# SSFocuser-C-TMC2208.net
KiCad netlist of a schematic drawn in Altium Designer
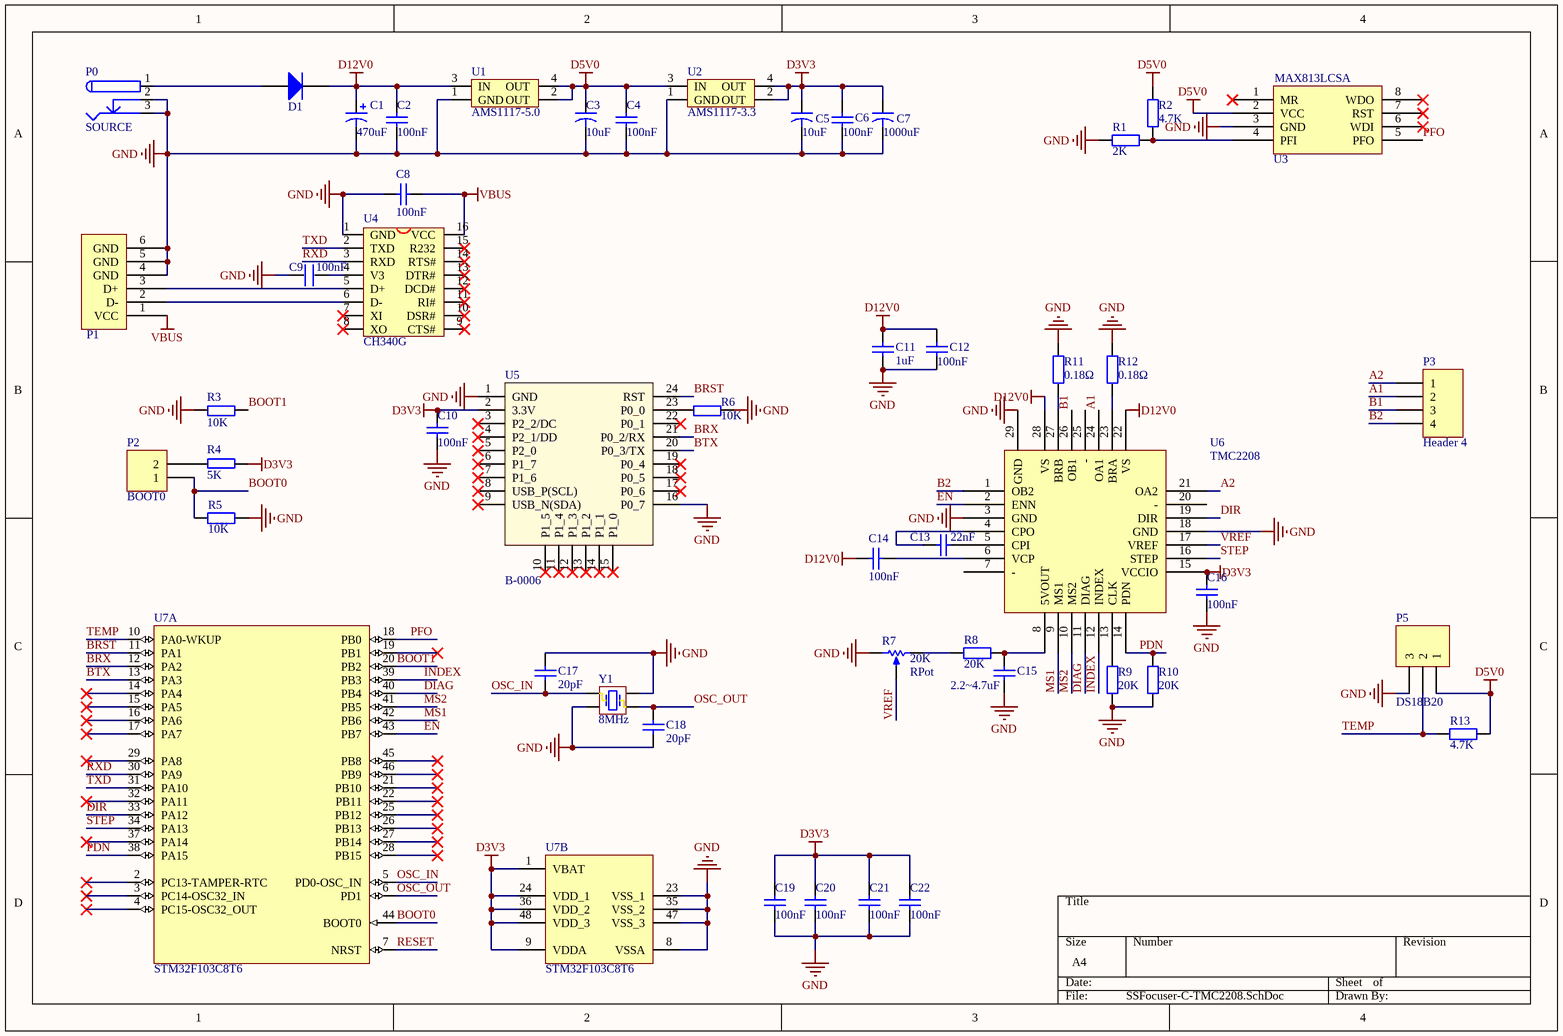
[diagram p0: SSFocuser-C-TMC2208.SchDoc]

(export (version "E")
  (design (tool "Eeschema 10.0.6"))
  (components
    (comp (ref "C1")
      (value "470uF")
      (footprint "16V/470U(CD10X10D5)")
      (description "470UF      16V      CD10X10D5")
      (libsource (lib "平台原理图symbol图库V1.0") (part "C470UF016S"))
    )
    (comp (ref "C2")
      (value "100nF")
      (footprint "0603C")
      (description "Capacitor")
      (fields (field (name "PUBLISHER") "Altium Limited"))
      (libsource (lib "Crazy_PCB") (part "Cap"))
    )
    (comp (ref "C3")
      (value "10uF")
      (footprint "3216")
      (fields (field (name "VAULE") "10uF"))
      (libsource (lib "Crazy_PCB") (part "CAP2"))
    )
    (comp (ref "C4")
      (value "100nF")
      (footprint "0603C")
      (description "Capacitor")
      (fields (field (name "PUBLISHER") "Altium Limited"))
      (libsource (lib "Crazy_PCB") (part "Cap"))
    )
    (comp (ref "C5")
      (value "10uF")
      (footprint "3216")
      (fields (field (name "VAULE") "10uF"))
      (libsource (lib "Crazy_PCB") (part "CAP2"))
    )
    (comp (ref "C6")
      (value "100nF")
      (footprint "0603C")
      (description "Capacitor")
      (fields (field (name "PUBLISHER") "Altium Limited"))
      (libsource (lib "Crazy_PCB") (part "Cap"))
    )
    (comp (ref "C7")
      (value "1000uF")
      (footprint "16V/470U(CD10X10D5)")
      (fields (field (name "VAULE") "1000uF"))
      (libsource (lib "Crazy_PCB") (part "CAP2"))
    )
    (comp (ref "C8")
      (value "100nF")
      (footprint "0603C")
      (description "Capacitor")
      (fields (field (name "PUBLISHER") "Altium Limited"))
      (libsource (lib "Crazy_PCB") (part "Cap"))
    )
    (comp (ref "C9")
      (value "100nF")
      (footprint "0603C")
      (libsource (lib "WarShip V3 STM32103封装库") (part "C"))
    )
    (comp (ref "C10")
      (value "100nF")
      (footprint "0603C")
      (description "Capacitor")
      (fields (field (name "PUBLISHER") "Altium Limited"))
      (libsource (lib "Crazy_PCB") (part "Cap"))
    )
    (comp (ref "C11")
      (value "1uF")
      (footprint "1206C")
      (description "Capacitor")
      (fields (field (name "PUBLISHER") "Altium Limited"))
      (libsource (lib "Crazy_PCB") (part "Cap"))
    )
    (comp (ref "C12")
      (value "100nF")
      (footprint "0603C")
      (description "Capacitor")
      (fields (field (name "PUBLISHER") "Altium Limited"))
      (libsource (lib "Crazy_PCB") (part "Cap"))
    )
    (comp (ref "C13")
      (value "22nF")
      (footprint "0603C")
      (description "Capacitor")
      (fields (field (name "PUBLISHER") "Altium Limited"))
      (libsource (lib "Crazy_PCB") (part "Cap"))
    )
    (comp (ref "C14")
      (value "100nF")
      (footprint "0603C")
      (description "Capacitor")
      (fields (field (name "PUBLISHER") "Altium Limited"))
      (libsource (lib "Crazy_PCB") (part "Cap"))
    )
    (comp (ref "C15")
      (value "2.2~4.7uF")
      (footprint "0603C")
      (description "Capacitor")
      (fields (field (name "PUBLISHER") "Altium Limited"))
      (libsource (lib "Crazy_PCB") (part "Cap"))
    )
    (comp (ref "C16")
      (value "100nF")
      (footprint "0603C")
      (description "Capacitor")
      (fields (field (name "PUBLISHER") "Altium Limited"))
      (libsource (lib "Crazy_PCB") (part "Cap"))
    )
    (comp (ref "C17")
      (value "20pF")
      (footprint "0603C")
      (description "Capacitor")
      (fields (field (name "PUBLISHER") "Altium Limited"))
      (libsource (lib "JL_SCH") (part "Cap"))
    )
    (comp (ref "C18")
      (value "20pF")
      (footprint "0603C")
      (description "Capacitor")
      (fields (field (name "PUBLISHER") "Altium Limited"))
      (libsource (lib "JL_SCH") (part "Cap"))
    )
    (comp (ref "C19")
      (value "100nF")
      (footprint "0603C")
      (description "Capacitor")
      (fields (field (name "PUBLISHER") "Altium Limited"))
      (libsource (lib "Crazy_PCB") (part "Cap"))
    )
    (comp (ref "C20")
      (value "100nF")
      (footprint "0603C")
      (description "Capacitor")
      (fields (field (name "PUBLISHER") "Altium Limited"))
      (libsource (lib "Crazy_PCB") (part "Cap"))
    )
    (comp (ref "C21")
      (value "100nF")
      (footprint "0603C")
      (description "Capacitor")
      (fields (field (name "PUBLISHER") "Altium Limited"))
      (libsource (lib "Crazy_PCB") (part "Cap"))
    )
    (comp (ref "C22")
      (value "100nF")
      (footprint "0603C")
      (description "Capacitor")
      (fields (field (name "PUBLISHER") "Altium Limited"))
      (libsource (lib "Crazy_PCB") (part "Cap"))
    )
    (comp (ref "D1")
      (value "M7")
      (footprint "DO-214AC")
      (description "High Conductance Fast Diode")
      (fields (field (name "PUBLISHER") "Altium Limited"))
      (libsource (lib "Crazy_PCB") (part "Diode"))
    )
    (comp (ref "P0")
      (value "SOURCE")
      (footprint "DC_5.5MM")
      (fields (field (name "PUBLISHER") "Altium Limited"))
      (libsource (lib "Crazy_PCB") (part "SOURCE"))
    )
    (comp (ref "P1") (value "USB-B") (footprint "USB-B") (libsource (lib "DX") (part "USB-B")))
    (comp (ref "P2")
      (value "BOOT0")
      (footprint "HDR1X2")
      (description "Header, 2-Pin")
      (fields (field (name "PUBLISHER") "Altium Limited"))
      (libsource (lib "Miscellaneous Connectors") (part "MHDR1X2"))
    )
    (comp (ref "P3")
      (value "Header 4")
      (footprint "XH_4_V")
      (description "Header, 4-Pin")
      (fields (field (name "PUBLISHER") "Altium Limited"))
      (libsource (lib "Miscellaneous Connectors") (part "Header 4"))
    )
    (comp (ref "P5")
      (value "DS18B20")
      (footprint "TO-92B")
      (description "Header, 3-Pin")
      (fields (field (name "PUBLISHER") "Altium Limited"))
      (libsource (lib "Miscellaneous Connectors") (part "Header 3"))
    )
    (comp (ref "R1")
      (value "2K")
      (footprint "0603R")
      (description "Resistor")
      (fields (field (name "PUBLISHER") "Altium Limited"))
      (libsource (lib "") (part "RES_2"))
    )
    (comp (ref "R2")
      (value "4.7K")
      (footprint "0603R")
      (description "Resistor")
      (fields (field (name "PUBLISHER") "Altium Limited"))
      (libsource (lib "") (part "RES_3"))
    )
    (comp (ref "R3") (value "10K") (footprint "0603R") (libsource (lib "WarShip V3 STM32103封装库") (part "R")))
    (comp (ref "R4") (value "5K") (footprint "0603R") (libsource (lib "WarShip V3 STM32103封装库") (part "R")))
    (comp (ref "R5")
      (value "10K")
      (footprint "0603R")
      (description "Resistor")
      (fields (field (name "PUBLISHER") "Altium Limited"))
      (libsource (lib "Crazy_PCB") (part "RES"))
    )
    (comp (ref "R6") (value "10K") (footprint "0603R") (libsource (lib "WarShip V3 STM32103封装库") (part "R")))
    (comp (ref "R7")
      (value "RPot")
      (footprint "VR_SMD")
      (description "Potentiometer")
      (fields (field (name "ALTIUM_VALUE") "20K") (field (name "PUBLISHER") "Altium Limited"))
      (libsource (lib "Miscellaneous Devices") (part "RPot"))
    )
    (comp (ref "R8")
      (value "20K")
      (footprint "0603R")
      (description "Resistor")
      (fields (field (name "PUBLISHER") "Altium Limited"))
      (libsource (lib "") (part "RES_2"))
    )
    (comp (ref "R9")
      (value "20K")
      (footprint "0603R")
      (description "Resistor")
      (fields (field (name "PUBLISHER") "Altium Limited"))
      (libsource (lib "") (part "RES_3"))
    )
    (comp (ref "R10")
      (value "20K")
      (footprint "0603R")
      (description "Resistor")
      (fields (field (name "PUBLISHER") "Altium Limited"))
      (libsource (lib "") (part "RES_3"))
    )
    (comp (ref "R11")
      (value "0.18Ω")
      (footprint "1206R")
      (description "Resistor")
      (fields (field (name "PUBLISHER") "Altium Limited"))
      (libsource (lib "") (part "RES_1"))
    )
    (comp (ref "R12")
      (value "0.18Ω")
      (footprint "1206R")
      (description "Resistor")
      (fields (field (name "PUBLISHER") "Altium Limited"))
      (libsource (lib "") (part "RES_1"))
    )
    (comp (ref "R13")
      (value "4.7K")
      (footprint "0603R")
      (description "Resistor")
      (fields (field (name "PUBLISHER") "Altium Limited"))
      (libsource (lib "Crazy_PCB") (part "RES"))
    )
    (comp (ref "U1")
      (value "AMS1117-5.0")
      (footprint "SOT223")
      (libsource (lib "MiniSTM32 V3.0封装库") (part "AMS1117"))
    )
    (comp (ref "U2")
      (value "AMS1117-3.3")
      (footprint "SOT223")
      (libsource (lib "MiniSTM32 V3.0封装库") (part "AMS1117"))
    )
    (comp (ref "U3") (value "MAX813LCSA") (footprint "SOP-8") (libsource (lib "DX") (part "MAX813L")))
    (comp (ref "U4")
      (value "CH340G")
      (footprint "SO-16")
      (description "USB2UART")
      (libsource (lib "WarShip V3 STM32103封装库") (part "CH340G"))
    )
    (comp (ref "U5") (value "B-0006") (footprint "B-0006") (libsource (lib "B-0006") (part "B-0006")))
    (comp (ref "U6") (value "TMC2208") (footprint "QFN28 5x5_M") (libsource (lib "SS") (part "TMC2208")))
    (comp (ref "U7")
      (value "STM32F103C8T6")
      (footprint "LQFP48_N")
      (libsource (lib "STMicroelectronics STM32 F1") (part "STM32F103C8T6"))
    )
    (comp (ref "Y1")
      (value "8MHz")
      (footprint "X3225")
      (description "Crystal Oscillator")
      (fields (field (name "PUBLISHER") "Altium Limited"))
      (libsource (lib "JL_SCH") (part "XTAL_1"))
    )
  )
  (nets
    (net (code "1") (name "/A1") (class "Default")
      (node (ref "P3") (pin "2") (pinfunction "2_2") (pintype "passive"))
      (node (ref "U6") (pin "24") (pinfunction "OA1_24") (pintype "passive"))
    )
    (net (code "2") (name "/A2") (class "Default")
      (node (ref "P3") (pin "1") (pinfunction "1_1") (pintype "passive"))
      (node (ref "U6") (pin "21") (pinfunction "OA2_21") (pintype "passive"))
    )
    (net (code "3") (name "/B1") (class "Default")
      (node (ref "P3") (pin "3") (pinfunction "3_3") (pintype "passive"))
      (node (ref "U6") (pin "26") (pinfunction "OB1_26") (pintype "passive"))
    )
    (net (code "4") (name "/B2") (class "Default")
      (node (ref "P3") (pin "4") (pinfunction "4_4") (pintype "passive"))
      (node (ref "U6") (pin "1") (pinfunction "OB2_1") (pintype "passive"))
    )
    (net (code "5") (name "/BOOT0") (class "Default")
      (node (ref "P2") (pin "1") (pinfunction "1_1") (pintype "passive"))
      (node (ref "R5") (pin "1") (pinfunction "1_1") (pintype "passive"))
      (node (ref "U7") (pin "44") (pinfunction "BOOT0_44") (pintype "input"))
    )
    (net (code "6") (name "/BOOT1") (class "Default")
      (node (ref "R3") (pin "2") (pintype "passive"))
      (node (ref "U7") (pin "20") (pinfunction "PB2_20") (pintype "bidirectional"))
    )
    (net (code "7") (name "/BRST") (class "Default")
      (node (ref "U5") (pin "24") (pinfunction "RST_24") (pintype "passive"))
      (node (ref "U7") (pin "11") (pinfunction "PA1_11") (pintype "bidirectional"))
    )
    (net (code "8") (name "/BRX") (class "Default")
      (node (ref "U5") (pin "21") (pinfunction "P0_2/RX_21") (pintype "passive"))
      (node (ref "U7") (pin "12") (pinfunction "PA2_12") (pintype "bidirectional"))
    )
    (net (code "9") (name "/BTX") (class "Default")
      (node (ref "U5") (pin "20") (pinfunction "P0_3/TX_20") (pintype "passive"))
      (node (ref "U7") (pin "13") (pinfunction "PA3_13") (pintype "bidirectional"))
    )
    (net (code "10") (name "/DIAG") (class "Default")
      (node (ref "U6") (pin "11") (pinfunction "DIAG_11") (pintype "passive"))
      (node (ref "U7") (pin "40") (pinfunction "PB4_40") (pintype "bidirectional"))
    )
    (net (code "11") (name "/DIR") (class "Default")
      (node (ref "U6") (pin "19") (pinfunction "DIR_19") (pintype "passive"))
      (node (ref "U7") (pin "33") (pinfunction "PA12_33") (pintype "bidirectional"))
    )
    (net (code "12") (name "/EN") (class "Default")
      (node (ref "U6") (pin "2") (pinfunction "ENN_2") (pintype "passive"))
      (node (ref "U7") (pin "43") (pinfunction "PB7_43") (pintype "bidirectional"))
    )
    (net (code "13") (name "/INDEX") (class "Default")
      (node (ref "U6") (pin "12") (pinfunction "INDEX_12") (pintype "passive"))
      (node (ref "U7") (pin "39") (pinfunction "PB3_39") (pintype "bidirectional"))
    )
    (net (code "14") (name "/MS1") (class "Default")
      (node (ref "U6") (pin "9") (pinfunction "MS1_9") (pintype "passive"))
      (node (ref "U7") (pin "42") (pinfunction "PB6_42") (pintype "bidirectional"))
    )
    (net (code "15") (name "/MS2") (class "Default")
      (node (ref "U6") (pin "10") (pinfunction "MS2_10") (pintype "passive"))
      (node (ref "U7") (pin "41") (pinfunction "PB5_41") (pintype "bidirectional"))
    )
    (net (code "16") (name "/OSC_IN") (class "Default")
      (node (ref "C17") (pin "1") (pinfunction "1_1") (pintype "passive"))
      (node (ref "U7") (pin "5") (pinfunction "PD0-OSC_IN_5") (pintype "bidirectional"))
      (node (ref "Y1") (pin "1") (pinfunction "OSC1_1") (pintype "passive"))
    )
    (net (code "17") (name "/OSC_OUT") (class "Default")
      (node (ref "C18") (pin "1") (pinfunction "1_1") (pintype "passive"))
      (node (ref "U7") (pin "6") (pinfunction "PD1_6") (pintype "bidirectional"))
      (node (ref "Y1") (pin "3") (pinfunction "OSC2_3") (pintype "passive"))
    )
    (net (code "18") (name "/PDN") (class "Default")
      (node (ref "R10") (pin "2") (pinfunction "2_2") (pintype "passive"))
      (node (ref "U6") (pin "14") (pinfunction "PDN_14") (pintype "passive"))
      (node (ref "U7") (pin "38") (pinfunction "PA15_38") (pintype "bidirectional"))
    )
    (net (code "19") (name "/PFO") (class "Default")
      (node (ref "U3") (pin "5") (pinfunction "PFO_5") (pintype "passive"))
      (node (ref "U7") (pin "18") (pinfunction "PB0_18") (pintype "bidirectional"))
    )
    (net (code "20") (name "/RESET") (class "Default")
      (node (ref "U7") (pin "7") (pinfunction "NRST_7") (pintype "bidirectional"))
    )
    (net (code "21") (name "/RXD") (class "Default")
      (node (ref "U4") (pin "3") (pinfunction "RXD_3") (pintype "passive"))
      (node (ref "U7") (pin "30") (pinfunction "PA9_30") (pintype "bidirectional"))
    )
    (net (code "22") (name "/STEP") (class "Default")
      (node (ref "U6") (pin "16") (pinfunction "STEP_16") (pintype "passive"))
      (node (ref "U7") (pin "34") (pinfunction "PA13_34") (pintype "bidirectional"))
    )
    (net (code "23") (name "/TEMP") (class "Default")
      (node (ref "P5") (pin "2") (pinfunction "2_2") (pintype "passive"))
      (node (ref "R13") (pin "1") (pinfunction "1_1") (pintype "passive"))
      (node (ref "U7") (pin "10") (pinfunction "PA0-WKUP_10") (pintype "bidirectional"))
    )
    (net (code "24") (name "/TXD") (class "Default")
      (node (ref "U4") (pin "2") (pinfunction "TXD_2") (pintype "passive"))
      (node (ref "U7") (pin "31") (pinfunction "PA10_31") (pintype "bidirectional"))
    )
    (net (code "25") (name "/VREF") (class "Default")
      (node (ref "R7") (pin "3") (pinfunction "TAP_3") (pintype "passive"))
      (node (ref "U6") (pin "17") (pinfunction "VREF_17") (pintype "passive"))
    )
    (net (code "26") (name "D3V3") (class "Default")
      (node (ref "C10") (pin "2") (pinfunction "2_2") (pintype "passive"))
      (node (ref "C16") (pin "2") (pinfunction "2_2") (pintype "passive"))
      (node (ref "C19") (pin "2") (pinfunction "2_2") (pintype "passive"))
      (node (ref "C20") (pin "2") (pinfunction "2_2") (pintype "passive"))
      (node (ref "C21") (pin "2") (pinfunction "2_2") (pintype "passive"))
      (node (ref "C22") (pin "2") (pinfunction "2_2") (pintype "passive"))
      (node (ref "C5") (pin "1") (pinfunction "1_1") (pintype "passive"))
      (node (ref "C6") (pin "2") (pinfunction "2_2") (pintype "passive"))
      (node (ref "C7") (pin "1") (pinfunction "1_1") (pintype "passive"))
      (node (ref "R4") (pin "1") (pintype "passive"))
      (node (ref "U2") (pin "2") (pinfunction "OUT_2") (pintype "passive"))
      (node (ref "U2") (pin "4") (pinfunction "OUT_4") (pintype "passive"))
      (node (ref "U5") (pin "2") (pinfunction "3.3V_2") (pintype "passive"))
      (node (ref "U6") (pin "15") (pinfunction "VCCIO_15") (pintype "passive"))
      (node (ref "U7") (pin "1") (pinfunction "VBAT_1") (pintype "power_in"))
      (node (ref "U7") (pin "24") (pinfunction "VDD_1_24") (pintype "power_in"))
      (node (ref "U7") (pin "36") (pinfunction "VDD_2_36") (pintype "power_in"))
      (node (ref "U7") (pin "48") (pinfunction "VDD_3_48") (pintype "power_in"))
      (node (ref "U7") (pin "9") (pinfunction "VDDA_9") (pintype "power_in"))
    )
    (net (code "27") (name "D5V0") (class "Default")
      (node (ref "C3") (pin "1") (pinfunction "1_1") (pintype "passive"))
      (node (ref "C4") (pin "2") (pinfunction "2_2") (pintype "passive"))
      (node (ref "P5") (pin "1") (pinfunction "1_1") (pintype "passive"))
      (node (ref "R13") (pin "2") (pinfunction "2_2") (pintype "passive"))
      (node (ref "R2") (pin "2") (pinfunction "2_2") (pintype "passive"))
      (node (ref "U1") (pin "2") (pinfunction "OUT_2") (pintype "passive"))
      (node (ref "U1") (pin "4") (pinfunction "OUT_4") (pintype "passive"))
      (node (ref "U2") (pin "3") (pinfunction "IN_3") (pintype "passive"))
      (node (ref "U3") (pin "2") (pinfunction "VCC_2") (pintype "passive"))
    )
    (net (code "28") (name "D12V0") (class "Default")
      (node (ref "C1") (pin "1") (pinfunction "1_1") (pintype "passive"))
      (node (ref "C11") (pin "1") (pinfunction "1_1") (pintype "passive"))
      (node (ref "C12") (pin "2") (pinfunction "2_2") (pintype "passive"))
      (node (ref "C14") (pin "2") (pinfunction "2_2") (pintype "passive"))
      (node (ref "C2") (pin "2") (pinfunction "2_2") (pintype "passive"))
      (node (ref "D1") (pin "2") (pinfunction "K_2") (pintype "passive"))
      (node (ref "U1") (pin "3") (pinfunction "IN_3") (pintype "passive"))
      (node (ref "U6") (pin "22") (pinfunction "VS_22") (pintype "passive"))
      (node (ref "U6") (pin "28") (pinfunction "VS_28") (pintype "passive"))
    )
    (net (code "29") (name "GND") (class "Default")
      (node (ref "C1") (pin "2") (pinfunction "2_2") (pintype "passive"))
      (node (ref "C10") (pin "1") (pinfunction "1_1") (pintype "passive"))
      (node (ref "C11") (pin "2") (pinfunction "2_2") (pintype "passive"))
      (node (ref "C12") (pin "1") (pinfunction "1_1") (pintype "passive"))
      (node (ref "C15") (pin "1") (pinfunction "1_1") (pintype "passive"))
      (node (ref "C16") (pin "1") (pinfunction "1_1") (pintype "passive"))
      (node (ref "C17") (pin "2") (pinfunction "2_2") (pintype "passive"))
      (node (ref "C18") (pin "2") (pinfunction "2_2") (pintype "passive"))
      (node (ref "C19") (pin "1") (pinfunction "1_1") (pintype "passive"))
      (node (ref "C2") (pin "1") (pinfunction "1_1") (pintype "passive"))
      (node (ref "C20") (pin "1") (pinfunction "1_1") (pintype "passive"))
      (node (ref "C21") (pin "1") (pinfunction "1_1") (pintype "passive"))
      (node (ref "C22") (pin "1") (pinfunction "1_1") (pintype "passive"))
      (node (ref "C3") (pin "2") (pinfunction "2_2") (pintype "passive"))
      (node (ref "C4") (pin "1") (pinfunction "1_1") (pintype "passive"))
      (node (ref "C5") (pin "2") (pinfunction "2_2") (pintype "passive"))
      (node (ref "C6") (pin "1") (pinfunction "1_1") (pintype "passive"))
      (node (ref "C7") (pin "2") (pinfunction "2_2") (pintype "passive"))
      (node (ref "C8") (pin "1") (pinfunction "1_1") (pintype "passive"))
      (node (ref "C9") (pin "1") (pintype "passive"))
      (node (ref "P0") (pin "2") (pinfunction "2_2") (pintype "power_in"))
      (node (ref "P0") (pin "3") (pinfunction "3_3") (pintype "power_in"))
      (node (ref "P1") (pin "4") (pinfunction "GND_4") (pintype "passive"))
      (node (ref "P1") (pin "5") (pinfunction "GND_5") (pintype "passive"))
      (node (ref "P1") (pin "6") (pinfunction "GND_6") (pintype "passive"))
      (node (ref "P5") (pin "3") (pinfunction "3_3") (pintype "passive"))
      (node (ref "R1") (pin "2") (pinfunction "2_2") (pintype "passive"))
      (node (ref "R10") (pin "1") (pinfunction "1_1") (pintype "passive"))
      (node (ref "R11") (pin "1") (pinfunction "1_1") (pintype "passive"))
      (node (ref "R12") (pin "1") (pinfunction "1_1") (pintype "passive"))
      (node (ref "R3") (pin "1") (pintype "passive"))
      (node (ref "R5") (pin "2") (pinfunction "2_2") (pintype "passive"))
      (node (ref "R6") (pin "2") (pintype "passive"))
      (node (ref "R7") (pin "1") (pinfunction "TOP_1") (pintype "passive"))
      (node (ref "R9") (pin "1") (pinfunction "1_1") (pintype "passive"))
      (node (ref "U1") (pin "1") (pinfunction "GND_1") (pintype "passive"))
      (node (ref "U2") (pin "1") (pinfunction "GND_1") (pintype "passive"))
      (node (ref "U3") (pin "3") (pinfunction "GND_3") (pintype "passive"))
      (node (ref "U4") (pin "1") (pinfunction "GND_1") (pintype "passive"))
      (node (ref "U5") (pin "1") (pinfunction "GND_1") (pintype "passive"))
      (node (ref "U5") (pin "16") (pinfunction "P0_7_16") (pintype "passive"))
      (node (ref "U6") (pin "18") (pinfunction "GND_18") (pintype "passive"))
      (node (ref "U6") (pin "29") (pinfunction "GND_29") (pintype "passive"))
      (node (ref "U6") (pin "3") (pinfunction "GND_3") (pintype "passive"))
      (node (ref "U7") (pin "23") (pinfunction "VSS_1_23") (pintype "power_in"))
      (node (ref "U7") (pin "35") (pinfunction "VSS_2_35") (pintype "power_in"))
      (node (ref "U7") (pin "47") (pinfunction "VSS_3_47") (pintype "power_in"))
      (node (ref "U7") (pin "8") (pinfunction "VSSA_8") (pintype "power_in"))
      (node (ref "Y1") (pin "2") (pinfunction "NA_2") (pintype "passive"))
      (node (ref "Y1") (pin "4") (pinfunction "NA_4") (pintype "passive"))
    )
    (net (code "30") (name "Net-(D1-A)") (class "Default")
      (node (ref "D1") (pin "1") (pinfunction "A_1") (pintype "passive"))
      (node (ref "P0") (pin "1") (pinfunction "1_1") (pintype "power_in"))
    )
    (net (code "31") (name "Net-(P1-D+)") (class "Default")
      (node (ref "P1") (pin "3") (pinfunction "D+_3") (pintype "passive"))
      (node (ref "U4") (pin "5") (pinfunction "D+_5") (pintype "passive"))
    )
    (net (code "32") (name "Net-(P1-D-)") (class "Default")
      (node (ref "P1") (pin "2") (pinfunction "D-_2") (pintype "passive"))
      (node (ref "U4") (pin "6") (pinfunction "D-_6") (pintype "passive"))
    )
    (net (code "33") (name "Net-(P2-Pad2)") (class "Default")
      (node (ref "P2") (pin "2") (pinfunction "2_2") (pintype "passive"))
      (node (ref "R4") (pin "2") (pintype "passive"))
    )
    (net (code "34") (name "Net-(R7-BOT)") (class "Default")
      (node (ref "R7") (pin "2") (pinfunction "BOT_2") (pintype "passive"))
      (node (ref "R8") (pin "2") (pinfunction "2_2") (pintype "passive"))
    )
    (net (code "35") (name "Net-(U3-PFI)") (class "Default")
      (node (ref "R1") (pin "1") (pinfunction "1_1") (pintype "passive"))
      (node (ref "R2") (pin "1") (pinfunction "1_1") (pintype "passive"))
      (node (ref "U3") (pin "4") (pinfunction "PFI_4") (pintype "passive"))
    )
    (net (code "36") (name "Net-(U4-V3)") (class "Default")
      (node (ref "C9") (pin "2") (pintype "passive"))
      (node (ref "U4") (pin "4") (pinfunction "V3_4") (pintype "passive"))
    )
    (net (code "37") (name "Net-(U5-P0_0)") (class "Default")
      (node (ref "R6") (pin "1") (pintype "passive"))
      (node (ref "U5") (pin "23") (pinfunction "P0_0_23") (pintype "passive"))
    )
    (net (code "38") (name "Net-(U6-5VOUT)") (class "Default")
      (node (ref "C15") (pin "2") (pinfunction "2_2") (pintype "passive"))
      (node (ref "R8") (pin "1") (pinfunction "1_1") (pintype "passive"))
      (node (ref "U6") (pin "8") (pinfunction "5VOUT_8") (pintype "passive"))
    )
    (net (code "39") (name "Net-(U6-BRA)") (class "Default")
      (node (ref "R12") (pin "2") (pinfunction "2_2") (pintype "passive"))
      (node (ref "U6") (pin "23") (pinfunction "BRA_23") (pintype "passive"))
    )
    (net (code "40") (name "Net-(U6-BRB)") (class "Default")
      (node (ref "R11") (pin "2") (pinfunction "2_2") (pintype "passive"))
      (node (ref "U6") (pin "27") (pinfunction "BRB_27") (pintype "passive"))
    )
    (net (code "41") (name "Net-(U6-CLK)") (class "Default")
      (node (ref "R9") (pin "2") (pinfunction "2_2") (pintype "passive"))
      (node (ref "U6") (pin "13") (pinfunction "CLK_13") (pintype "passive"))
    )
    (net (code "42") (name "Net-(U6-CPI)") (class "Default")
      (node (ref "C13") (pin "1") (pinfunction "1_1") (pintype "passive"))
      (node (ref "U6") (pin "5") (pinfunction "CPI_5") (pintype "passive"))
    )
    (net (code "43") (name "Net-(U6-CPO)") (class "Default")
      (node (ref "C13") (pin "2") (pinfunction "2_2") (pintype "passive"))
      (node (ref "U6") (pin "4") (pinfunction "CPO_4") (pintype "passive"))
    )
    (net (code "44") (name "Net-(U6-VCP)") (class "Default")
      (node (ref "C14") (pin "1") (pinfunction "1_1") (pintype "passive"))
      (node (ref "U6") (pin "6") (pinfunction "VCP_6") (pintype "passive"))
    )
    (net (code "45") (name "VBUS") (class "Default")
      (node (ref "C8") (pin "2") (pinfunction "2_2") (pintype "passive"))
      (node (ref "P1") (pin "1") (pinfunction "VCC_1") (pintype "passive"))
      (node (ref "U4") (pin "16") (pinfunction "VCC_16") (pintype "passive"))
    )
    (net (code "46") (name "unconnected-(U3-MR-Pad1)") (class "Default")
      (node (ref "U3") (pin "1") (pinfunction "MR_1") (pintype "passive+no_connect"))
    )
    (net (code "47") (name "unconnected-(U3-RST-Pad7)") (class "Default")
      (node (ref "U3") (pin "7") (pinfunction "RST_7") (pintype "passive+no_connect"))
    )
    (net (code "48") (name "unconnected-(U3-WDI-Pad6)") (class "Default")
      (node (ref "U3") (pin "6") (pinfunction "WDI_6") (pintype "passive+no_connect"))
    )
    (net (code "49") (name "unconnected-(U3-WDO-Pad8)") (class "Default")
      (node (ref "U3") (pin "8") (pinfunction "WDO_8") (pintype "passive+no_connect"))
    )
    (net (code "50") (name "unconnected-(U4-CTS#-Pad9)") (class "Default")
      (node (ref "U4") (pin "9") (pinfunction "CTS#_9") (pintype "passive+no_connect"))
    )
    (net (code "51") (name "unconnected-(U4-DCD#-Pad12)") (class "Default")
      (node (ref "U4") (pin "12") (pinfunction "DCD#_12") (pintype "passive+no_connect"))
    )
    (net (code "52") (name "unconnected-(U4-DSR#-Pad10)") (class "Default")
      (node (ref "U4") (pin "10") (pinfunction "DSR#_10") (pintype "passive+no_connect"))
    )
    (net (code "53") (name "unconnected-(U4-DTR#-Pad13)") (class "Default")
      (node (ref "U4") (pin "13") (pinfunction "DTR#_13") (pintype "passive+no_connect"))
    )
    (net (code "54") (name "unconnected-(U4-R232-Pad15)") (class "Default")
      (node (ref "U4") (pin "15") (pinfunction "R232_15") (pintype "passive+no_connect"))
    )
    (net (code "55") (name "unconnected-(U4-RI#-Pad11)") (class "Default")
      (node (ref "U4") (pin "11") (pinfunction "RI#_11") (pintype "passive+no_connect"))
    )
    (net (code "56") (name "unconnected-(U4-RTS#-Pad14)") (class "Default")
      (node (ref "U4") (pin "14") (pinfunction "RTS#_14") (pintype "passive+no_connect"))
    )
    (net (code "57") (name "unconnected-(U4-XI-Pad7)") (class "Default")
      (node (ref "U4") (pin "7") (pinfunction "XI_7") (pintype "passive+no_connect"))
    )
    (net (code "58") (name "unconnected-(U4-XO-Pad8)") (class "Default")
      (node (ref "U4") (pin "8") (pinfunction "XO_8") (pintype "passive+no_connect"))
    )
    (net (code "59") (name "unconnected-(U5-P0_1-Pad22)") (class "Default")
      (node (ref "U5") (pin "22") (pinfunction "P0_1_22") (pintype "passive+no_connect"))
    )
    (net (code "60") (name "unconnected-(U5-P0_4-Pad19)") (class "Default")
      (node (ref "U5") (pin "19") (pinfunction "P0_4_19") (pintype "passive+no_connect"))
    )
    (net (code "61") (name "unconnected-(U5-P0_5-Pad18)") (class "Default")
      (node (ref "U5") (pin "18") (pinfunction "P0_5_18") (pintype "passive+no_connect"))
    )
    (net (code "62") (name "unconnected-(U5-P0_6-Pad17)") (class "Default")
      (node (ref "U5") (pin "17") (pinfunction "P0_6_17") (pintype "passive+no_connect"))
    )
    (net (code "63") (name "unconnected-(U5-P1_0-Pad15)") (class "Default")
      (node (ref "U5") (pin "15") (pinfunction "P1_0_15") (pintype "passive+no_connect"))
    )
    (net (code "64") (name "unconnected-(U5-P1_1-Pad14)") (class "Default")
      (node (ref "U5") (pin "14") (pinfunction "P1_1_14") (pintype "passive+no_connect"))
    )
    (net (code "65") (name "unconnected-(U5-P1_2-Pad13)") (class "Default")
      (node (ref "U5") (pin "13") (pinfunction "P1_2_13") (pintype "passive+no_connect"))
    )
    (net (code "66") (name "unconnected-(U5-P1_3-Pad12)") (class "Default")
      (node (ref "U5") (pin "12") (pinfunction "P1_3_12") (pintype "passive+no_connect"))
    )
    (net (code "67") (name "unconnected-(U5-P1_4-Pad11)") (class "Default")
      (node (ref "U5") (pin "11") (pinfunction "P1_4_11") (pintype "passive+no_connect"))
    )
    (net (code "68") (name "unconnected-(U5-P1_5-Pad10)") (class "Default")
      (node (ref "U5") (pin "10") (pinfunction "P1_5_10") (pintype "passive+no_connect"))
    )
    (net (code "69") (name "unconnected-(U5-P1_6-Pad7)") (class "Default")
      (node (ref "U5") (pin "7") (pinfunction "P1_6_7") (pintype "passive+no_connect"))
    )
    (net (code "70") (name "unconnected-(U5-P1_7-Pad6)") (class "Default")
      (node (ref "U5") (pin "6") (pinfunction "P1_7_6") (pintype "passive+no_connect"))
    )
    (net (code "71") (name "unconnected-(U5-P2_0-Pad5)") (class "Default")
      (node (ref "U5") (pin "5") (pinfunction "P2_0_5") (pintype "passive+no_connect"))
    )
    (net (code "72") (name "unconnected-(U5-P2_1{slash}DD-Pad4)") (class "Default")
      (node (ref "U5") (pin "4") (pinfunction "P2_1/DD_4") (pintype "passive+no_connect"))
    )
    (net (code "73") (name "unconnected-(U5-P2_2{slash}DC-Pad3)") (class "Default")
      (node (ref "U5") (pin "3") (pinfunction "P2_2/DC_3") (pintype "passive+no_connect"))
    )
    (net (code "74") (name "unconnected-(U5-USB_N(SDA)-Pad9)") (class "Default")
      (node (ref "U5") (pin "9") (pinfunction "USB_N(SDA)_9") (pintype "passive+no_connect"))
    )
    (net (code "75") (name "unconnected-(U5-USB_P(SCL)-Pad8)") (class "Default")
      (node (ref "U5") (pin "8") (pinfunction "USB_P(SCL)_8") (pintype "passive+no_connect"))
    )
    (net (code "76") (name "unconnected-(U6---Pad7)") (class "Default")
      (node (ref "U6") (pin "7") (pinfunction "-_7") (pintype "passive"))
    )
    (net (code "77") (name "unconnected-(U6---Pad20)") (class "Default")
      (node (ref "U6") (pin "20") (pinfunction "-_20") (pintype "passive"))
    )
    (net (code "78") (name "unconnected-(U6---Pad25)") (class "Default")
      (node (ref "U6") (pin "25") (pinfunction "-_25") (pintype "passive"))
    )
    (net (code "79") (name "unconnected-(U7A-PA4-Pad14)") (class "Default")
      (node (ref "U7") (pin "14") (pinfunction "PA4_14") (pintype "bidirectional+no_connect"))
    )
    (net (code "80") (name "unconnected-(U7A-PA5-Pad15)") (class "Default")
      (node (ref "U7") (pin "15") (pinfunction "PA5_15") (pintype "bidirectional+no_connect"))
    )
    (net (code "81") (name "unconnected-(U7A-PA6-Pad16)") (class "Default")
      (node (ref "U7") (pin "16") (pinfunction "PA6_16") (pintype "bidirectional+no_connect"))
    )
    (net (code "82") (name "unconnected-(U7A-PA7-Pad17)") (class "Default")
      (node (ref "U7") (pin "17") (pinfunction "PA7_17") (pintype "bidirectional+no_connect"))
    )
    (net (code "83") (name "unconnected-(U7A-PA8-Pad29)") (class "Default")
      (node (ref "U7") (pin "29") (pinfunction "PA8_29") (pintype "bidirectional+no_connect"))
    )
    (net (code "84") (name "unconnected-(U7A-PA11-Pad32)") (class "Default")
      (node (ref "U7") (pin "32") (pinfunction "PA11_32") (pintype "bidirectional+no_connect"))
    )
    (net (code "85") (name "unconnected-(U7A-PA14-Pad37)") (class "Default")
      (node (ref "U7") (pin "37") (pinfunction "PA14_37") (pintype "bidirectional+no_connect"))
    )
    (net (code "86") (name "unconnected-(U7A-PB1-Pad19)") (class "Default")
      (node (ref "U7") (pin "19") (pinfunction "PB1_19") (pintype "bidirectional+no_connect"))
    )
    (net (code "87") (name "unconnected-(U7A-PB8-Pad45)") (class "Default")
      (node (ref "U7") (pin "45") (pinfunction "PB8_45") (pintype "bidirectional+no_connect"))
    )
    (net (code "88") (name "unconnected-(U7A-PB9-Pad46)") (class "Default")
      (node (ref "U7") (pin "46") (pinfunction "PB9_46") (pintype "bidirectional+no_connect"))
    )
    (net (code "89") (name "unconnected-(U7A-PB10-Pad21)") (class "Default")
      (node (ref "U7") (pin "21") (pinfunction "PB10_21") (pintype "bidirectional+no_connect"))
    )
    (net (code "90") (name "unconnected-(U7A-PB11-Pad22)") (class "Default")
      (node (ref "U7") (pin "22") (pinfunction "PB11_22") (pintype "bidirectional+no_connect"))
    )
    (net (code "91") (name "unconnected-(U7A-PB12-Pad25)") (class "Default")
      (node (ref "U7") (pin "25") (pinfunction "PB12_25") (pintype "bidirectional+no_connect"))
    )
    (net (code "92") (name "unconnected-(U7A-PB13-Pad26)") (class "Default")
      (node (ref "U7") (pin "26") (pinfunction "PB13_26") (pintype "bidirectional+no_connect"))
    )
    (net (code "93") (name "unconnected-(U7A-PB14-Pad27)") (class "Default")
      (node (ref "U7") (pin "27") (pinfunction "PB14_27") (pintype "bidirectional+no_connect"))
    )
    (net (code "94") (name "unconnected-(U7A-PB15-Pad28)") (class "Default")
      (node (ref "U7") (pin "28") (pinfunction "PB15_28") (pintype "bidirectional+no_connect"))
    )
    (net (code "95") (name "unconnected-(U7A-PC13-TAMPER-RTC-Pad2)") (class "Default")
      (node (ref "U7") (pin "2") (pinfunction "PC13-TAMPER-RTC_2") (pintype "bidirectional+no_connect"))
    )
    (net (code "96") (name "unconnected-(U7A-PC14-OSC32_IN-Pad3)") (class "Default")
      (node (ref "U7") (pin "3") (pinfunction "PC14-OSC32_IN_3") (pintype "bidirectional+no_connect"))
    )
    (net (code "97") (name "unconnected-(U7A-PC15-OSC32_OUT-Pad4)") (class "Default")
      (node (ref "U7") (pin "4") (pinfunction "PC15-OSC32_OUT_4") (pintype "bidirectional+no_connect"))
    )
  )
)
